# receiver.net
KiCad netlist of a schematic drawn in EAGLE
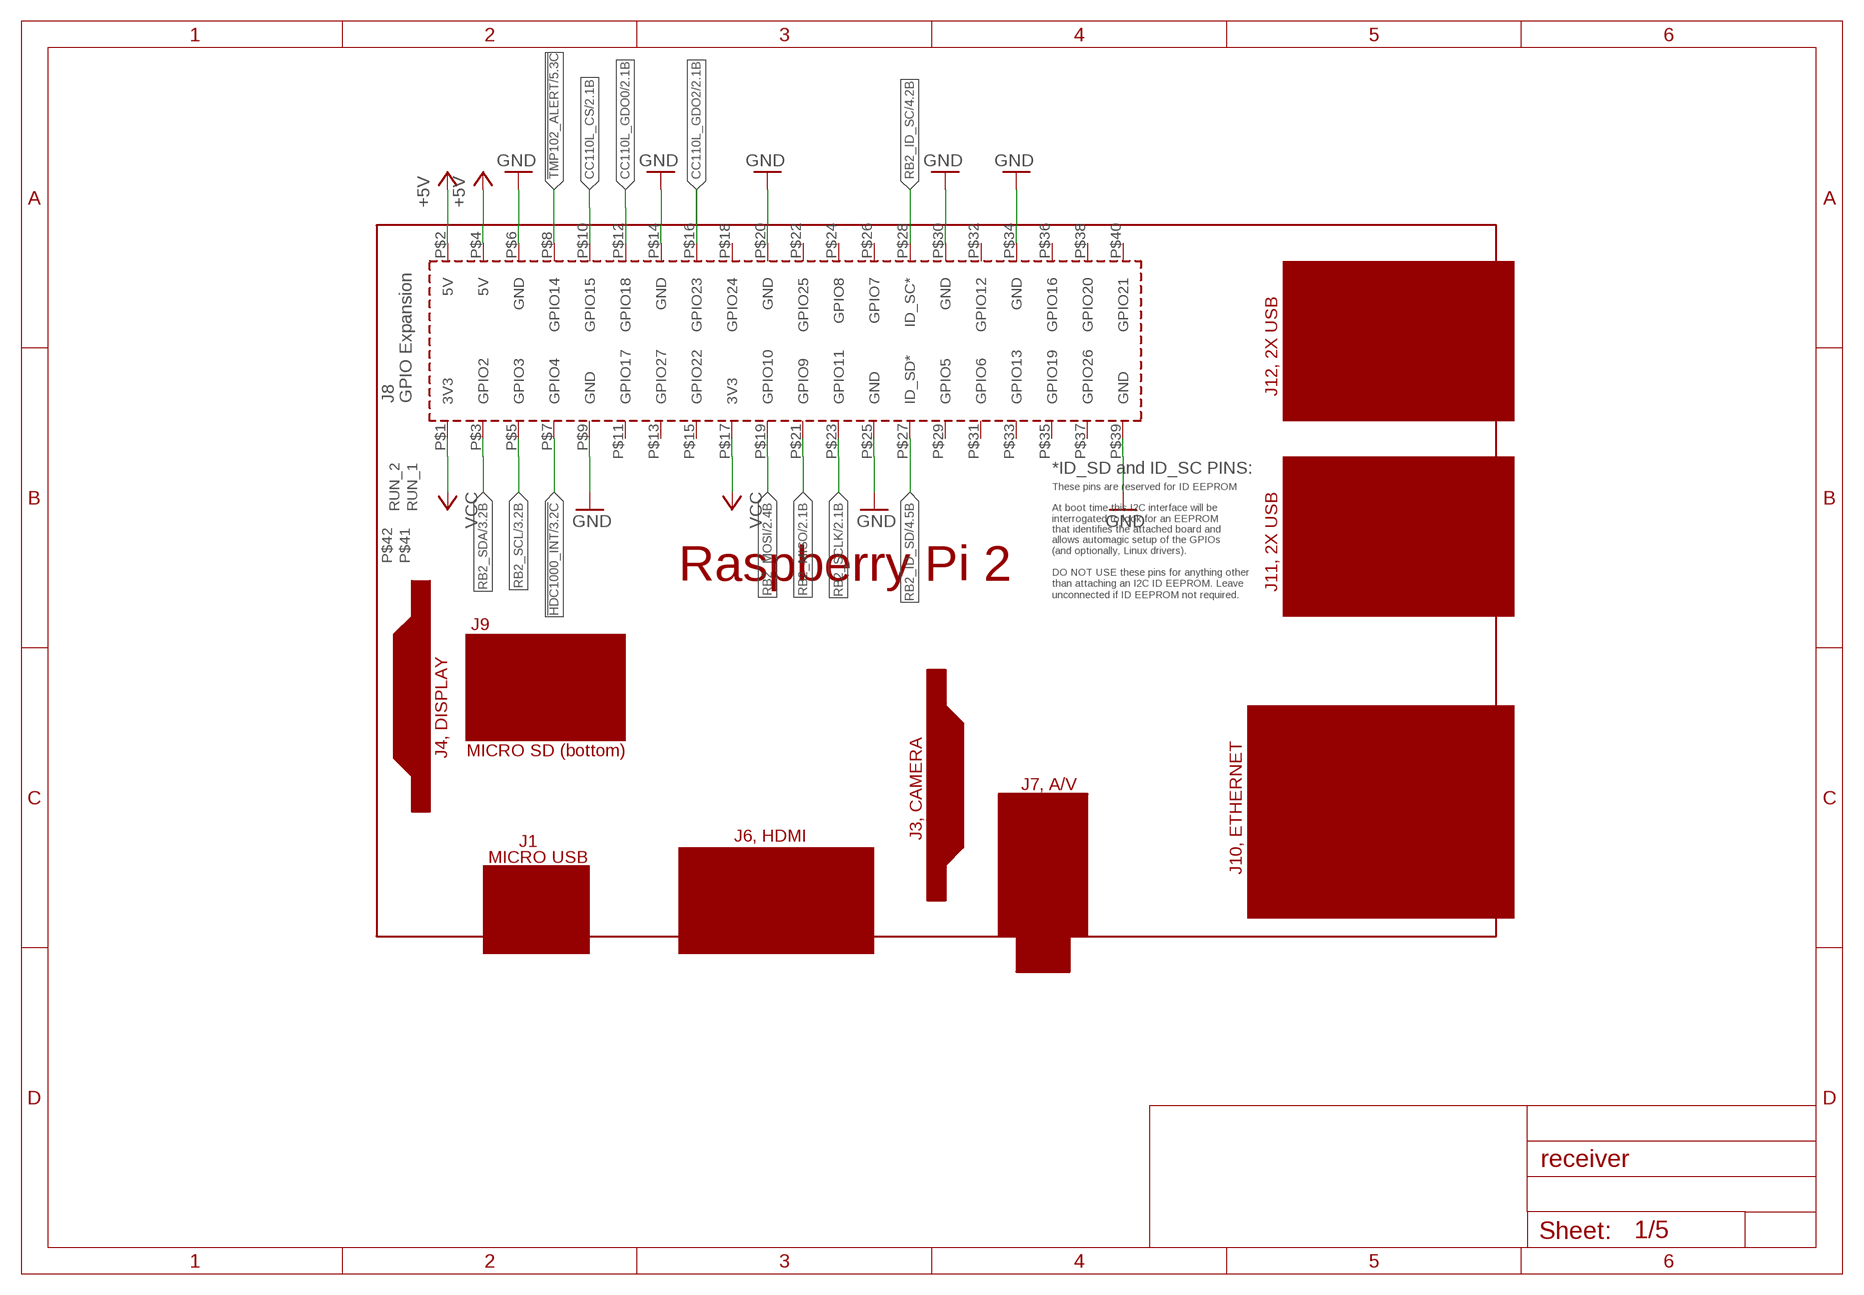
[diagram p0: schematic, sheet 1]
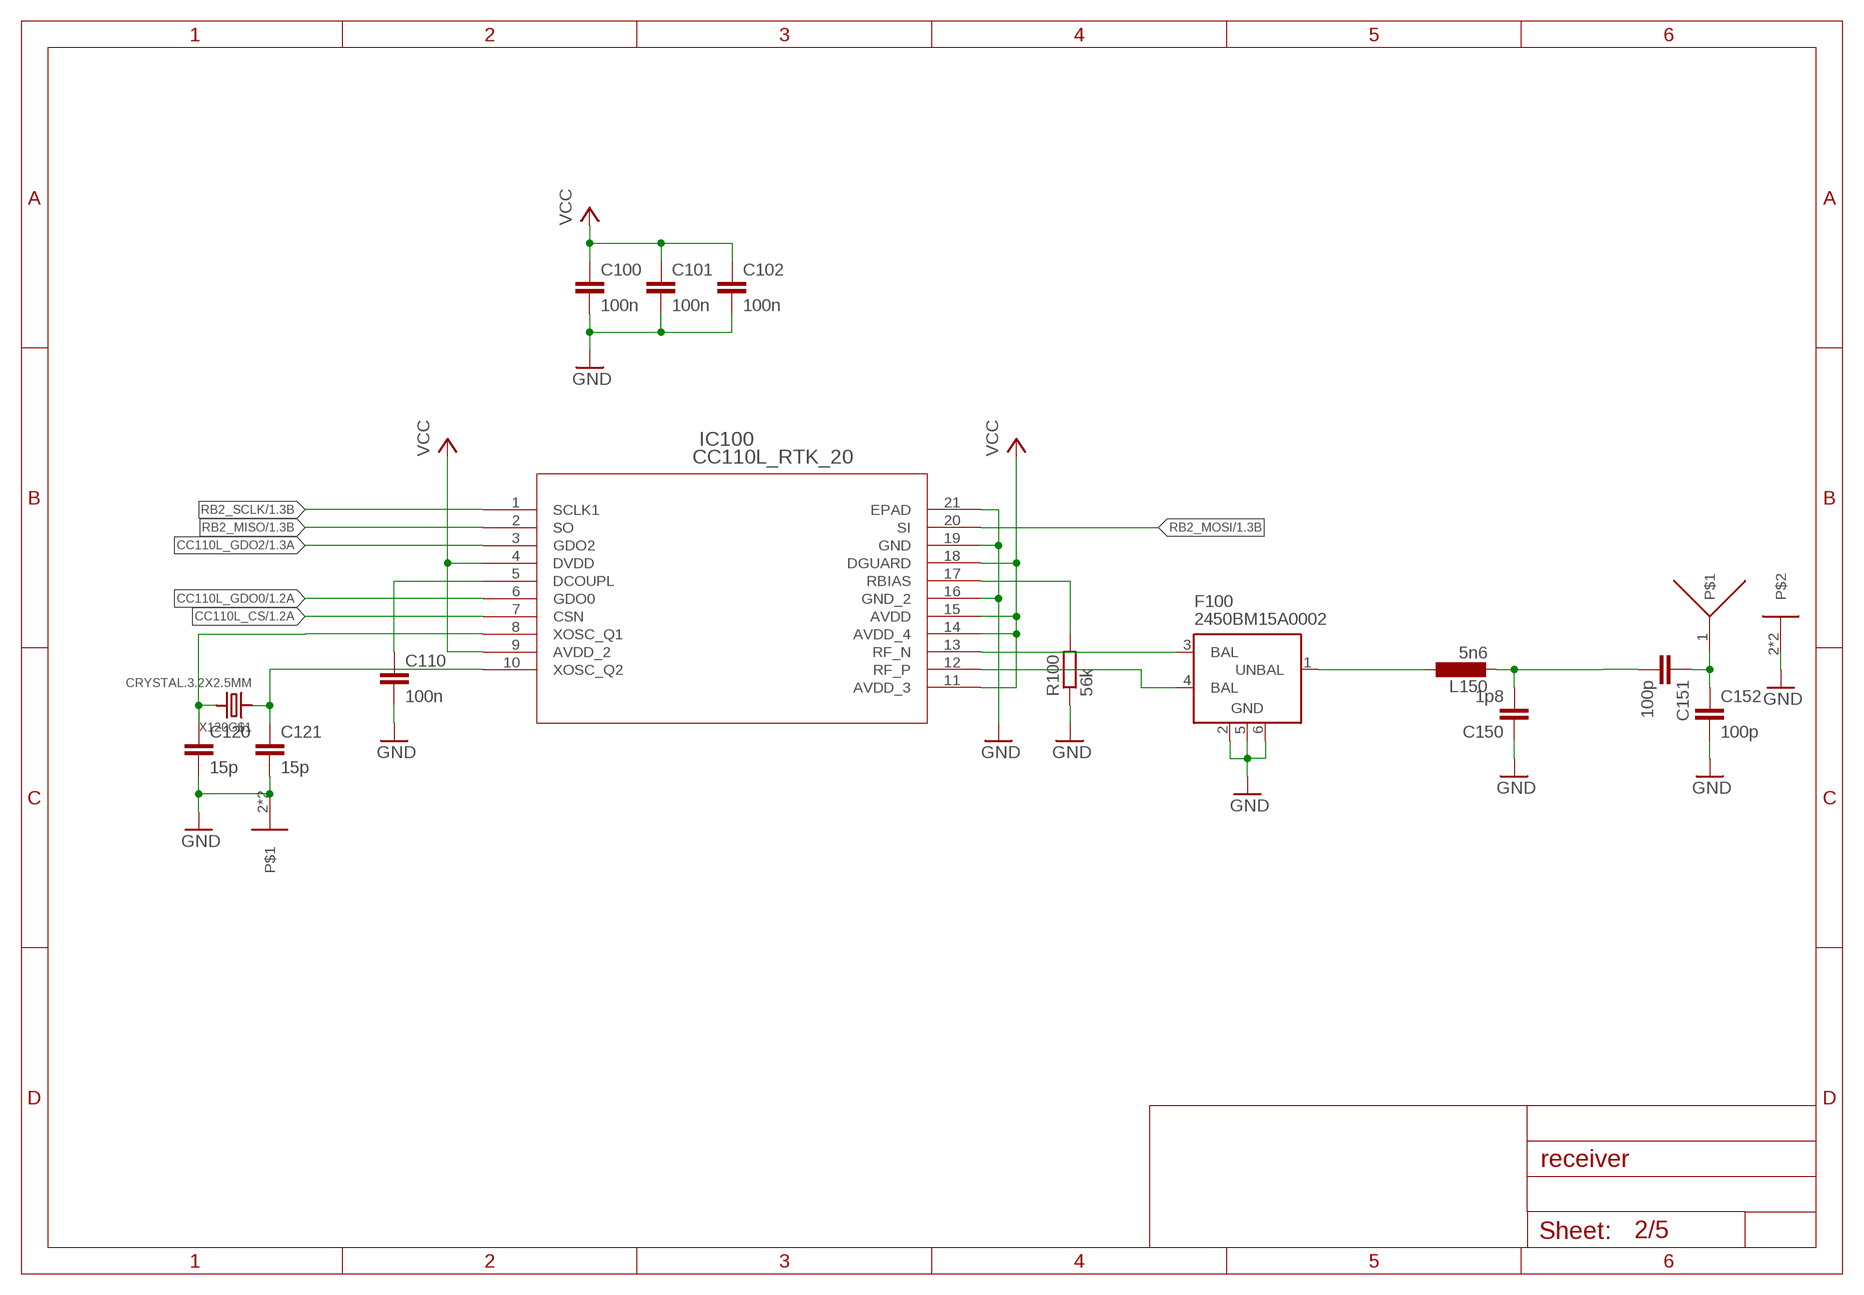
[diagram p1: schematic, sheet 2]
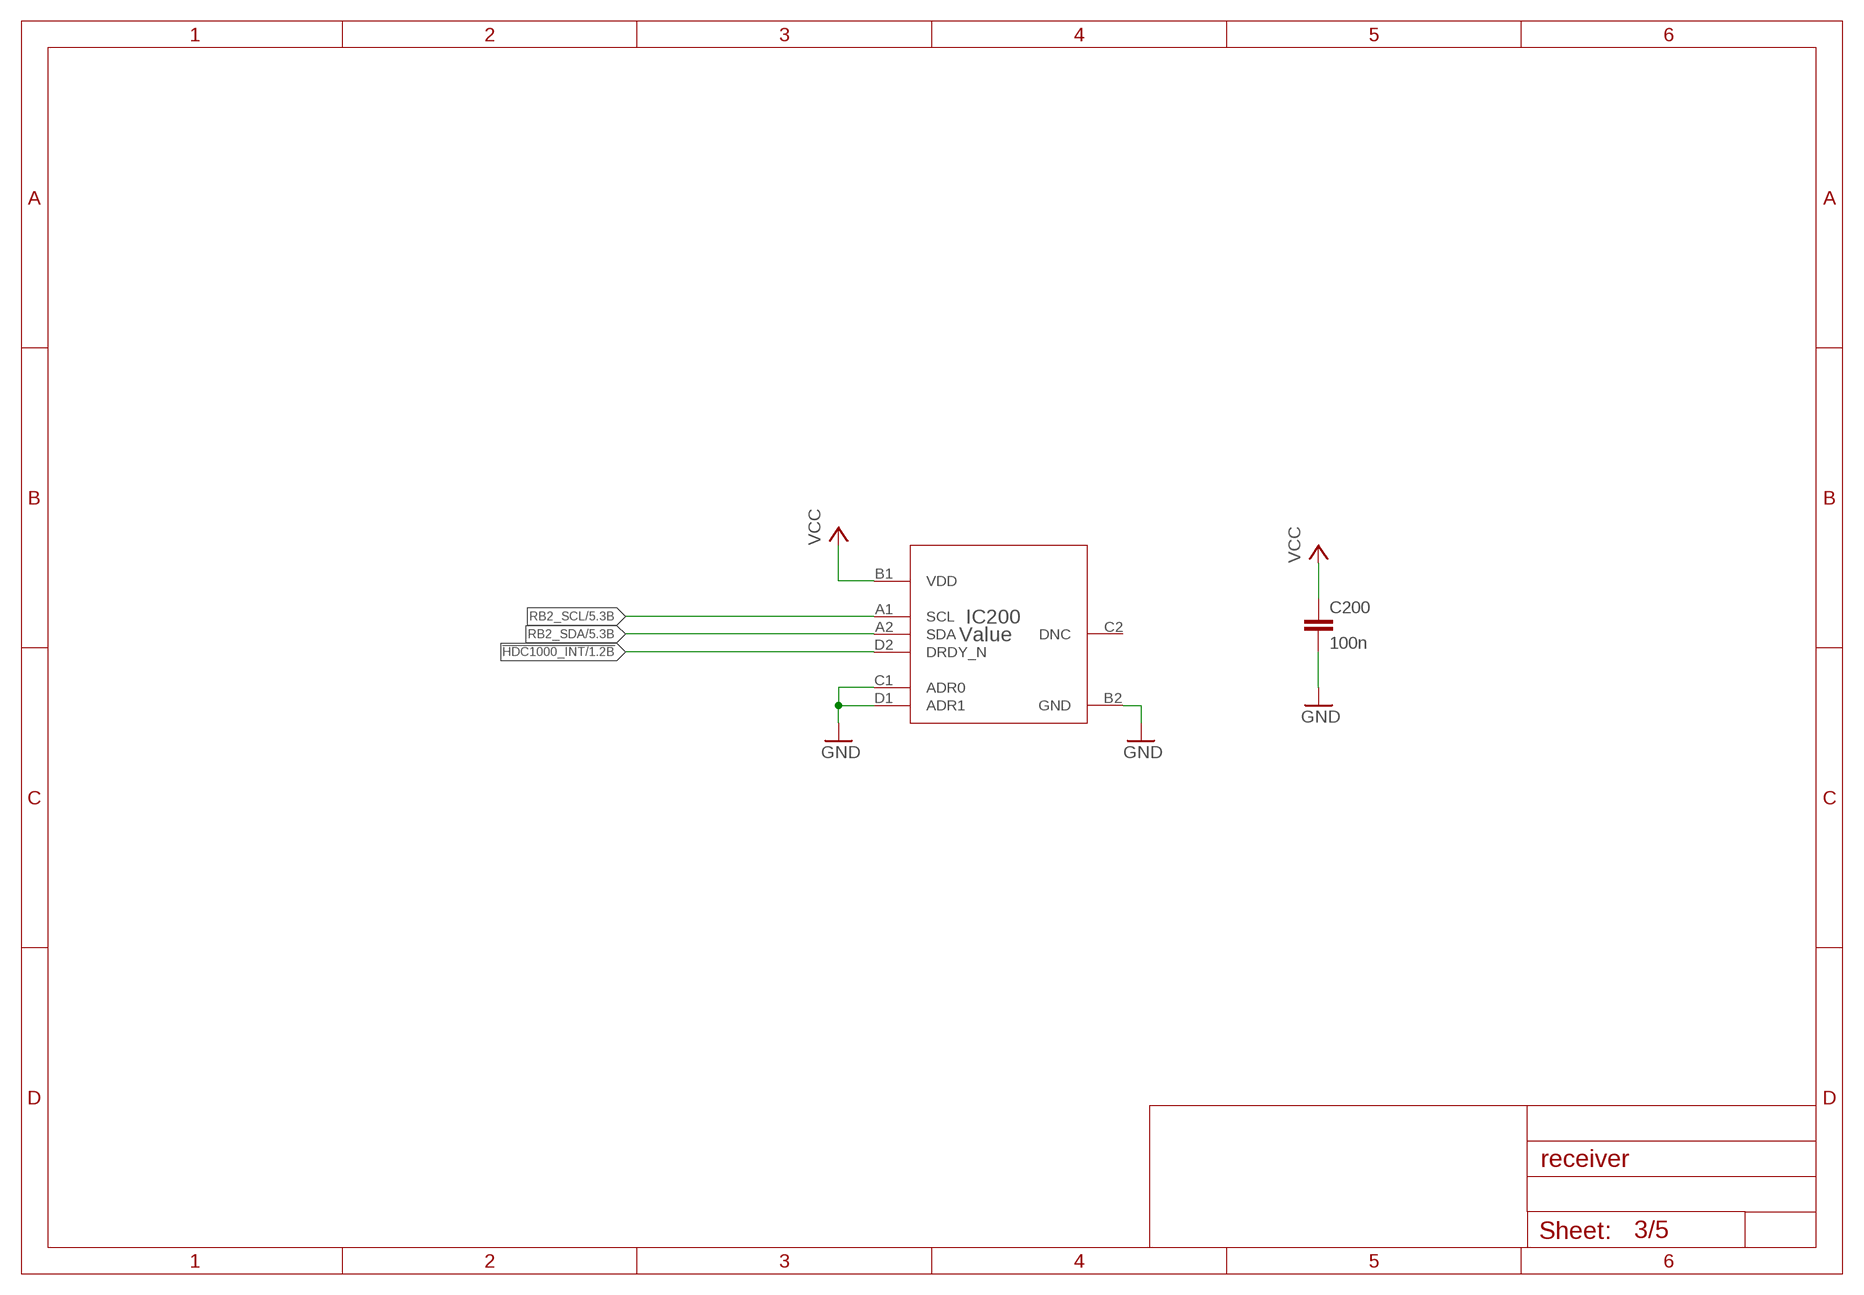
[diagram p2: schematic, sheet 3]
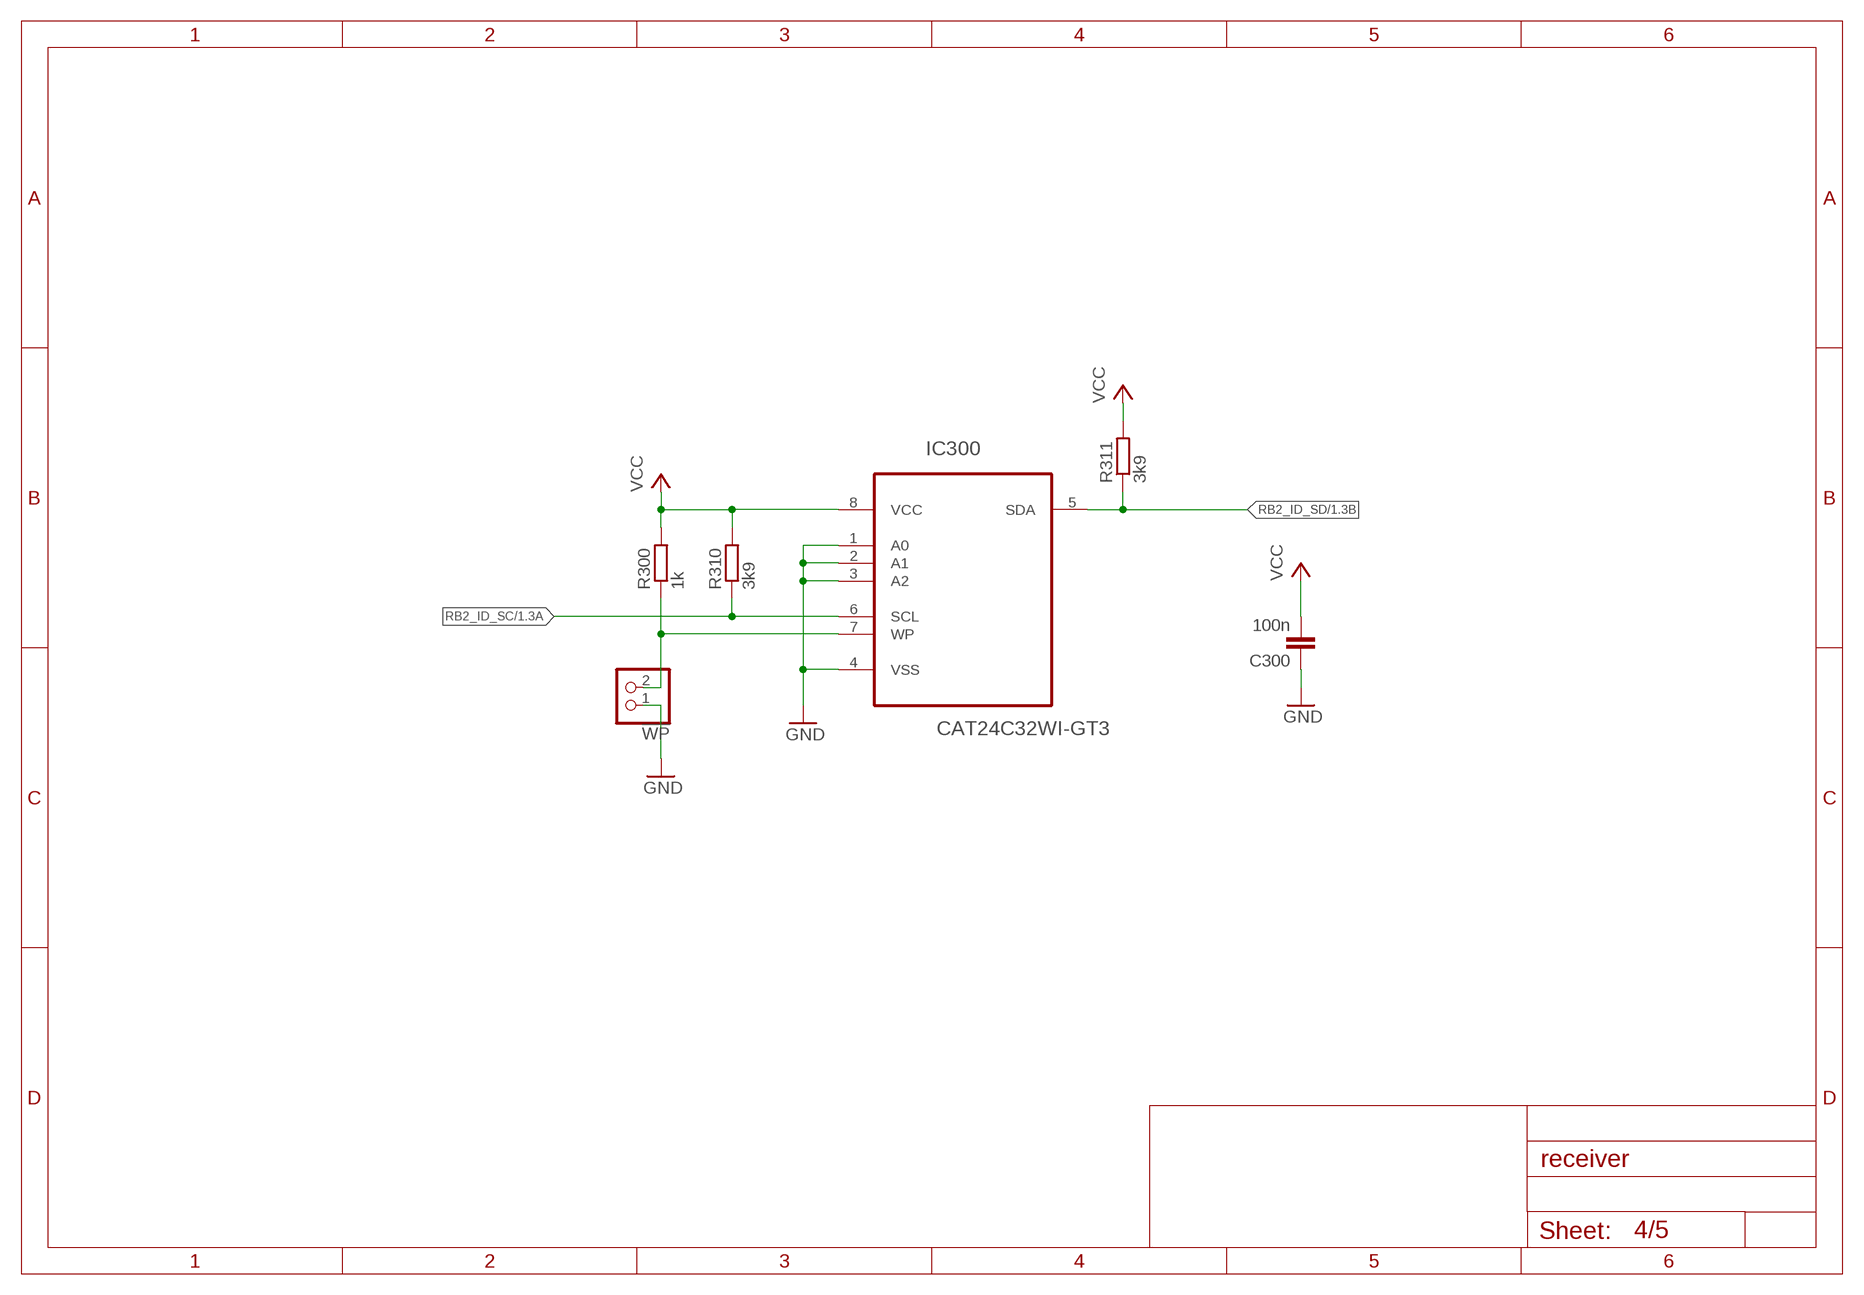
[diagram p3: schematic, sheet 4]
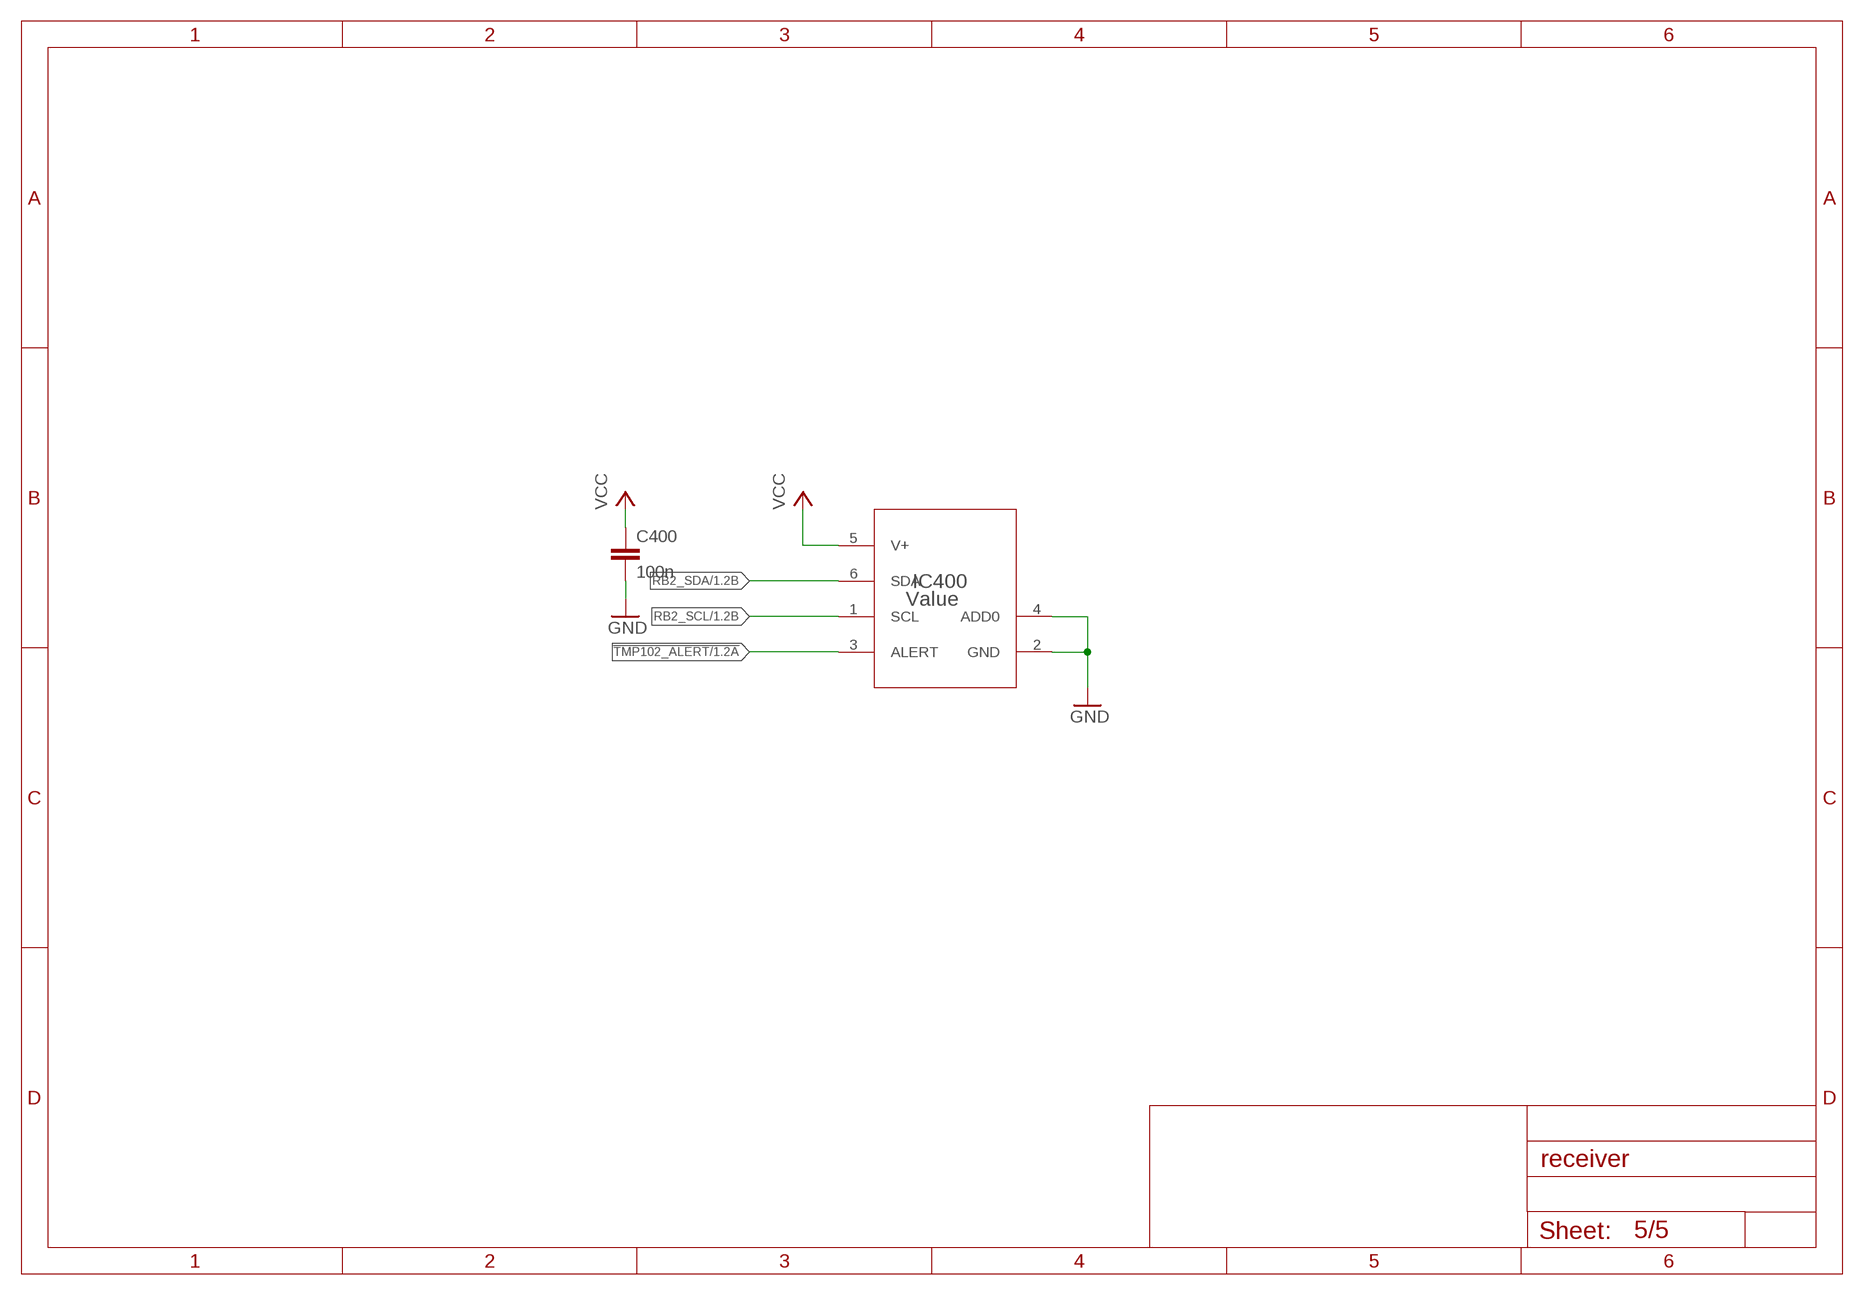
[diagram p4: schematic, sheet 5]

(export (version "E")
  (design (tool "Eeschema 10.0.6"))
  (components
    (comp (ref "C100")
      (value "100n")
      (footprint "eagle-import:C0603")
      (libsource (lib "eagle-import") (part "C-EUC0603"))
    )
    (comp (ref "C101")
      (value "100n")
      (footprint "eagle-import:C0603")
      (libsource (lib "eagle-import") (part "C-EUC0603"))
    )
    (comp (ref "C102")
      (value "100n")
      (footprint "eagle-import:C0603")
      (libsource (lib "eagle-import") (part "C-EUC0603"))
    )
    (comp (ref "C110")
      (value "100n")
      (footprint "eagle-import:C0603")
      (libsource (lib "eagle-import") (part "C-EUC0603"))
    )
    (comp (ref "C120")
      (value "15p")
      (footprint "eagle-import:C0603")
      (libsource (lib "eagle-import") (part "C-EUC0603"))
    )
    (comp (ref "C121")
      (value "15p")
      (footprint "eagle-import:C0603")
      (libsource (lib "eagle-import") (part "C-EUC0603"))
    )
    (comp (ref "C150")
      (value "1p8")
      (footprint "eagle-import:C0603K")
      (libsource (lib "eagle-import") (part "C-EUC0603K"))
    )
    (comp (ref "C151")
      (value "100p")
      (footprint "eagle-import:C0603")
      (libsource (lib "eagle-import") (part "C-EUC0603"))
    )
    (comp (ref "C152")
      (value "100p")
      (footprint "eagle-import:C0603K")
      (libsource (lib "eagle-import") (part "C-EUC0603K"))
    )
    (comp (ref "F100")
      (value "2450BM15A0002")
      (footprint "eagle-import:2450BM15A0002")
      (libsource (lib "eagle-import") (part "2450BM15A0002"))
    )
    (comp (ref "IC100")
      (value "CC110L_RTK_20")
      (footprint "eagle-import:RTK20_2P4X2P4")
      (fields (field (name "GENERIC_PART_NUMBER") "CC110L") (field (name "MANUFACTURER") "Texas Instruments"))
      (libsource (lib "eagle-import") (part "CC110L_RTK_20"))
    )
    (comp (ref "L150")
      (value "5n6")
      (footprint "eagle-import:L2012C")
      (libsource (lib "eagle-import") (part "L-EUL2012C"))
    )
    (comp (ref "R100")
      (value "56k")
      (footprint "eagle-import:R0603")
      (libsource (lib "eagle-import") (part "R-EU_R0603"))
    )
    (comp (ref "U$1")
      (value "ANTENNA868W3013-INV")
      (footprint "eagle-import:W3013-INV")
      (libsource (lib "eagle-import") (part "ANTENNA868W3013-INV"))
    )
    (comp (ref "X120")
      (value "CRYSTAL.3.2X2.5MM")
      (footprint "eagle-import:3.2X2.5MM")
      (libsource (lib "eagle-import") (part "CRYSTAL.3.2X2.5MM"))
    )
    (comp (ref "PCB1")
      (value "RPI2")
      (footprint "eagle-import:RPI2")
      (libsource (lib "eagle-import") (part "RPI2"))
    )
    (comp (ref "C200")
      (value "100n")
      (footprint "eagle-import:C0603")
      (libsource (lib "eagle-import") (part "C-EUC0603"))
    )
    (comp (ref "IC200")
      (value "Value")
      (footprint "eagle-import:YPA0008AGAE")
      (fields
        (field (name "ALTERNATEPARTNUMBER") "HDC1000YPAT")
        (field (name "MANUFACTURER") "Texas Instruments")
        (field (name "PARTNUMBER") "HDC1000YPAR")
      )
      (libsource (lib "eagle-import") (part "HDC1000YPAR"))
    )
    (comp (ref "C400")
      (value "100n")
      (footprint "eagle-import:C0603")
      (libsource (lib "eagle-import") (part "C-EUC0603"))
    )
    (comp (ref "IC400")
      (value "Value")
      (footprint "eagle-import:DRL0006A")
      (fields (field (name "MANUFACTURER") "Texas Instruments") (field (name "PARTNUMBER") "TMP102AQDRLRQ1"))
      (libsource (lib "eagle-import") (part "TMP102AQDRLRQ1"))
    )
    (comp (ref "!WP")
      (value "PINHD-1X2")
      (footprint "eagle-import:1X02")
      (libsource (lib "eagle-import") (part "PINHD-1X2"))
    )
    (comp (ref "C300")
      (value "100n")
      (footprint "eagle-import:C0603")
      (libsource (lib "eagle-import") (part "C-EUC0603"))
    )
    (comp (ref "IC300")
      (value "CAT24C32WI-GT3")
      (footprint "eagle-import:SOIC127P600X175-8N")
      (libsource (lib "eagle-import") (part "CAT24C32WI-GT3"))
    )
    (comp (ref "R300")
      (value "1k")
      (footprint "eagle-import:R0603")
      (libsource (lib "eagle-import") (part "R-EU_R0603"))
    )
    (comp (ref "R310")
      (value "3k9")
      (footprint "eagle-import:R0603")
      (libsource (lib "eagle-import") (part "R-EU_R0603"))
    )
    (comp (ref "R311")
      (value "3k9")
      (footprint "eagle-import:R0603")
      (libsource (lib "eagle-import") (part "R-EU_R0603"))
    )
  )
  (nets
    (net (code "1") (name "+5V") (class "Default")
      (node (ref "PCB1") (pin "P$2") (pinfunction "5V_P$2") (pintype "bidirectional"))
      (node (ref "PCB1") (pin "P$4") (pinfunction "5V_P$4") (pintype "bidirectional"))
    )
    (net (code "2") (name "CC110L_CS") (class "Default")
      (node (ref "IC100") (pin "7") (pinfunction "CSN_7") (pintype "passive"))
      (node (ref "PCB1") (pin "P$10") (pinfunction "GPIO15_P$10") (pintype "bidirectional"))
    )
    (net (code "3") (name "CC110L_GDO0") (class "Default")
      (node (ref "IC100") (pin "6") (pinfunction "GDO0_6") (pintype "output"))
      (node (ref "PCB1") (pin "P$12") (pinfunction "GPIO18_P$12") (pintype "bidirectional"))
    )
    (net (code "4") (name "CC110L_GDO2") (class "Default")
      (node (ref "IC100") (pin "3") (pinfunction "GDO2_3") (pintype "output"))
      (node (ref "PCB1") (pin "P$16") (pinfunction "GPIO23_P$16") (pintype "bidirectional"))
    )
    (net (code "5") (name "GND") (class "Default")
      (node (ref "!WP") (pin "1") (pinfunction "1_1") (pintype "passive"))
      (node (ref "C100") (pin "2") (pinfunction "2_2") (pintype "passive"))
      (node (ref "C101") (pin "2") (pinfunction "2_2") (pintype "passive"))
      (node (ref "C102") (pin "2") (pinfunction "2_2") (pintype "passive"))
      (node (ref "C110") (pin "2") (pinfunction "2_2") (pintype "passive"))
      (node (ref "C120") (pin "2") (pinfunction "2_2") (pintype "passive"))
      (node (ref "C121") (pin "2") (pinfunction "2_2") (pintype "passive"))
      (node (ref "C150") (pin "1") (pinfunction "1_1") (pintype "passive"))
      (node (ref "C152") (pin "2") (pinfunction "2_2") (pintype "passive"))
      (node (ref "C200") (pin "2") (pinfunction "2_2") (pintype "passive"))
      (node (ref "C300") (pin "1") (pinfunction "1_1") (pintype "passive"))
      (node (ref "C400") (pin "2") (pinfunction "2_2") (pintype "passive"))
      (node (ref "F100") (pin "2") (pinfunction "GND_2") (pintype "passive"))
      (node (ref "F100") (pin "5") (pinfunction "GND_5") (pintype "passive"))
      (node (ref "F100") (pin "6") (pinfunction "GND_6") (pintype "passive"))
      (node (ref "IC100") (pin "16") (pinfunction "GND_2_16") (pintype "power_in"))
      (node (ref "IC100") (pin "19") (pinfunction "GND_19") (pintype "power_in"))
      (node (ref "IC100") (pin "21") (pinfunction "EPAD_21") (pintype "power_in"))
      (node (ref "IC200") (pin "B2") (pinfunction "GND_B2") (pintype "power_in"))
      (node (ref "IC200") (pin "C1") (pinfunction "ADR0_C1") (pintype "input"))
      (node (ref "IC200") (pin "D1") (pinfunction "ADR1_D1") (pintype "input"))
      (node (ref "IC300") (pin "1") (pinfunction "A0_1") (pintype "input"))
      (node (ref "IC300") (pin "2") (pinfunction "A1_2") (pintype "input"))
      (node (ref "IC300") (pin "3") (pinfunction "A2_3") (pintype "input"))
      (node (ref "IC300") (pin "4") (pinfunction "VSS_4") (pintype "passive"))
      (node (ref "IC400") (pin "2") (pinfunction "GND_2") (pintype "power_in"))
      (node (ref "IC400") (pin "4") (pinfunction "ADD0_4") (pintype "input"))
      (node (ref "PCB1") (pin "P$14") (pinfunction "GND_P$14") (pintype "bidirectional"))
      (node (ref "PCB1") (pin "P$20") (pinfunction "GND_P$20") (pintype "bidirectional"))
      (node (ref "PCB1") (pin "P$25") (pinfunction "GND_P$25") (pintype "bidirectional"))
      (node (ref "PCB1") (pin "P$30") (pinfunction "GND_P$30") (pintype "bidirectional"))
      (node (ref "PCB1") (pin "P$34") (pinfunction "GND_P$34") (pintype "bidirectional"))
      (node (ref "PCB1") (pin "P$39") (pinfunction "GND_P$39") (pintype "bidirectional"))
      (node (ref "PCB1") (pin "P$6") (pinfunction "GND_P$6") (pintype "bidirectional"))
      (node (ref "PCB1") (pin "P$9") (pinfunction "GND_P$9") (pintype "bidirectional"))
      (node (ref "R100") (pin "1") (pinfunction "1_1") (pintype "passive"))
      (node (ref "U$1") (pin "2") (pinfunction "P$2_2") (pintype "bidirectional"))
      (node (ref "U$1") (pin "3") (pinfunction "P$2_3") (pintype "bidirectional"))
      (node (ref "X120") (pin "2") (pinfunction "P$1_2") (pintype "bidirectional"))
      (node (ref "X120") (pin "4") (pinfunction "P$1_4") (pintype "bidirectional"))
    )
    (net (code "6") (name "Net-(C150-Pad2)") (class "Default")
      (node (ref "C150") (pin "2") (pinfunction "2_2") (pintype "passive"))
      (node (ref "C151") (pin "2") (pinfunction "2_2") (pintype "passive"))
      (node (ref "L150") (pin "2") (pinfunction "2_2") (pintype "passive"))
    )
    (net (code "7") (name "Net-(F100-UNBAL)") (class "Default")
      (node (ref "F100") (pin "1") (pinfunction "UNBAL_1") (pintype "passive"))
      (node (ref "L150") (pin "1") (pinfunction "1_1") (pintype "passive"))
    )
    (net (code "8") (name "Net-(IC100-DCOUPL)") (class "Default")
      (node (ref "C110") (pin "1") (pinfunction "1_1") (pintype "passive"))
      (node (ref "IC100") (pin "5") (pinfunction "DCOUPL_5") (pintype "passive"))
    )
    (net (code "9") (name "Net-(IC100-RBIAS)") (class "Default")
      (node (ref "IC100") (pin "17") (pinfunction "RBIAS_17") (pintype "passive"))
      (node (ref "R100") (pin "2") (pinfunction "2_2") (pintype "passive"))
    )
    (net (code "10") (name "Net-(IC100-RF_N)") (class "Default")
      (node (ref "F100") (pin "3") (pinfunction "BAL_3") (pintype "passive"))
      (node (ref "IC100") (pin "13") (pinfunction "RF_N_13") (pintype "passive"))
    )
    (net (code "11") (name "Net-(IC100-RF_P)") (class "Default")
      (node (ref "F100") (pin "4") (pinfunction "BAL_4") (pintype "passive"))
      (node (ref "IC100") (pin "12") (pinfunction "RF_P_12") (pintype "passive"))
    )
    (net (code "12") (name "Net-(IC100-XOSC_Q1)") (class "Default")
      (node (ref "C120") (pin "1") (pinfunction "1_1") (pintype "passive"))
      (node (ref "IC100") (pin "8") (pinfunction "XOSC_Q1_8") (pintype "passive"))
      (node (ref "X120") (pin "3") (pinfunction "2_3") (pintype "passive"))
    )
    (net (code "13") (name "Net-(IC100-XOSC_Q2)") (class "Default")
      (node (ref "C121") (pin "1") (pinfunction "1_1") (pintype "passive"))
      (node (ref "IC100") (pin "10") (pinfunction "XOSC_Q2_10") (pintype "passive"))
      (node (ref "X120") (pin "1") (pinfunction "1_1") (pintype "passive"))
    )
    (net (code "14") (name "Net-(IC300-WP)") (class "Default")
      (node (ref "!WP") (pin "2") (pinfunction "2_2") (pintype "passive"))
      (node (ref "IC300") (pin "7") (pinfunction "WP_7") (pintype "input"))
      (node (ref "R300") (pin "1") (pinfunction "1_1") (pintype "passive"))
    )
    (net (code "15") (name "Net-(U$1-P$1)") (class "Default")
      (node (ref "C151") (pin "1") (pinfunction "1_1") (pintype "passive"))
      (node (ref "C152") (pin "1") (pinfunction "1_1") (pintype "passive"))
      (node (ref "U$1") (pin "1") (pinfunction "P$1_1") (pintype "bidirectional"))
    )
    (net (code "16") (name "RB2_ID_SC") (class "Default")
      (node (ref "IC300") (pin "6") (pinfunction "SCL_6") (pintype "input"))
      (node (ref "PCB1") (pin "P$28") (pinfunction "ID_SC*_P$28") (pintype "bidirectional"))
      (node (ref "R310") (pin "1") (pinfunction "1_1") (pintype "passive"))
    )
    (net (code "17") (name "RB2_ID_SD") (class "Default")
      (node (ref "IC300") (pin "5") (pinfunction "SDA_5") (pintype "bidirectional"))
      (node (ref "PCB1") (pin "P$27") (pinfunction "ID_SD*_P$27") (pintype "bidirectional"))
      (node (ref "R311") (pin "1") (pinfunction "1_1") (pintype "passive"))
    )
    (net (code "18") (name "RB2_MISO") (class "Default")
      (node (ref "IC100") (pin "2") (pinfunction "SO_2") (pintype "output"))
      (node (ref "PCB1") (pin "P$21") (pinfunction "GPIO9_P$21") (pintype "bidirectional"))
    )
    (net (code "19") (name "RB2_MOSI") (class "Default")
      (node (ref "IC100") (pin "20") (pinfunction "SI_20") (pintype "input"))
      (node (ref "PCB1") (pin "P$19") (pinfunction "GPIO10_P$19") (pintype "bidirectional"))
    )
    (net (code "20") (name "RB2_SCL") (class "Default")
      (node (ref "IC200") (pin "A1") (pinfunction "SCL_A1") (pintype "input"))
      (node (ref "IC400") (pin "1") (pinfunction "SCL_1") (pintype "bidirectional"))
      (node (ref "PCB1") (pin "P$5") (pinfunction "GPIO3_P$5") (pintype "bidirectional"))
    )
    (net (code "21") (name "RB2_SCLK") (class "Default")
      (node (ref "IC100") (pin "1") (pinfunction "SCLK1_1") (pintype "passive"))
      (node (ref "PCB1") (pin "P$23") (pinfunction "GPIO11_P$23") (pintype "bidirectional"))
    )
    (net (code "22") (name "RB2_SDA") (class "Default")
      (node (ref "IC200") (pin "A2") (pinfunction "SDA_A2") (pintype "bidirectional"))
      (node (ref "IC400") (pin "6") (pinfunction "SDA_6") (pintype "bidirectional"))
      (node (ref "PCB1") (pin "P$3") (pinfunction "GPIO2_P$3") (pintype "bidirectional"))
    )
    (net (code "23") (name "VCC") (class "Default")
      (node (ref "C100") (pin "1") (pinfunction "1_1") (pintype "passive"))
      (node (ref "C101") (pin "1") (pinfunction "1_1") (pintype "passive"))
      (node (ref "C102") (pin "1") (pinfunction "1_1") (pintype "passive"))
      (node (ref "C200") (pin "1") (pinfunction "1_1") (pintype "passive"))
      (node (ref "C300") (pin "2") (pinfunction "2_2") (pintype "passive"))
      (node (ref "C400") (pin "1") (pinfunction "1_1") (pintype "passive"))
      (node (ref "IC100") (pin "11") (pinfunction "AVDD_3_11") (pintype "power_in"))
      (node (ref "IC100") (pin "14") (pinfunction "AVDD_4_14") (pintype "power_in"))
      (node (ref "IC100") (pin "15") (pinfunction "AVDD_15") (pintype "power_in"))
      (node (ref "IC100") (pin "18") (pinfunction "DGUARD_18") (pintype "passive"))
      (node (ref "IC100") (pin "4") (pinfunction "DVDD_4") (pintype "power_in"))
      (node (ref "IC100") (pin "9") (pinfunction "AVDD_2_9") (pintype "power_in"))
      (node (ref "IC200") (pin "B1") (pinfunction "VDD_B1") (pintype "power_in"))
      (node (ref "IC300") (pin "8") (pinfunction "VCC_8") (pintype "power_in"))
      (node (ref "IC400") (pin "5") (pinfunction "V+_5") (pintype "power_in"))
      (node (ref "PCB1") (pin "P$1") (pinfunction "3V3_P$1") (pintype "bidirectional"))
      (node (ref "PCB1") (pin "P$17") (pinfunction "3V3_P$17") (pintype "bidirectional"))
      (node (ref "R300") (pin "2") (pinfunction "2_2") (pintype "passive"))
      (node (ref "R310") (pin "2") (pinfunction "2_2") (pintype "passive"))
      (node (ref "R311") (pin "2") (pinfunction "2_2") (pintype "passive"))
    )
    (net (code "24") (name "unconnected-(IC200-DNC-PadC2)") (class "Default")
      (node (ref "IC200") (pin "C2") (pinfunction "DNC_C2") (pintype "passive"))
    )
    (net (code "25") (name "unconnected-(PCB1-GPIO5-PadP$29)") (class "Default")
      (node (ref "PCB1") (pin "P$29") (pinfunction "GPIO5_P$29") (pintype "bidirectional"))
    )
    (net (code "26") (name "unconnected-(PCB1-GPIO6-PadP$31)") (class "Default")
      (node (ref "PCB1") (pin "P$31") (pinfunction "GPIO6_P$31") (pintype "bidirectional"))
    )
    (net (code "27") (name "unconnected-(PCB1-GPIO7-PadP$26)") (class "Default")
      (node (ref "PCB1") (pin "P$26") (pinfunction "GPIO7_P$26") (pintype "bidirectional"))
    )
    (net (code "28") (name "unconnected-(PCB1-GPIO8-PadP$24)") (class "Default")
      (node (ref "PCB1") (pin "P$24") (pinfunction "GPIO8_P$24") (pintype "bidirectional"))
    )
    (net (code "29") (name "unconnected-(PCB1-GPIO12-PadP$32)") (class "Default")
      (node (ref "PCB1") (pin "P$32") (pinfunction "GPIO12_P$32") (pintype "bidirectional"))
    )
    (net (code "30") (name "unconnected-(PCB1-GPIO13-PadP$33)") (class "Default")
      (node (ref "PCB1") (pin "P$33") (pinfunction "GPIO13_P$33") (pintype "bidirectional"))
    )
    (net (code "31") (name "unconnected-(PCB1-GPIO16-PadP$36)") (class "Default")
      (node (ref "PCB1") (pin "P$36") (pinfunction "GPIO16_P$36") (pintype "bidirectional"))
    )
    (net (code "32") (name "unconnected-(PCB1-GPIO17-PadP$11)") (class "Default")
      (node (ref "PCB1") (pin "P$11") (pinfunction "GPIO17_P$11") (pintype "bidirectional"))
    )
    (net (code "33") (name "unconnected-(PCB1-GPIO19-PadP$35)") (class "Default")
      (node (ref "PCB1") (pin "P$35") (pinfunction "GPIO19_P$35") (pintype "bidirectional"))
    )
    (net (code "34") (name "unconnected-(PCB1-GPIO20-PadP$38)") (class "Default")
      (node (ref "PCB1") (pin "P$38") (pinfunction "GPIO20_P$38") (pintype "bidirectional"))
    )
    (net (code "35") (name "unconnected-(PCB1-GPIO21-PadP$40)") (class "Default")
      (node (ref "PCB1") (pin "P$40") (pinfunction "GPIO21_P$40") (pintype "bidirectional"))
    )
    (net (code "36") (name "unconnected-(PCB1-GPIO22-PadP$15)") (class "Default")
      (node (ref "PCB1") (pin "P$15") (pinfunction "GPIO22_P$15") (pintype "bidirectional"))
    )
    (net (code "37") (name "unconnected-(PCB1-GPIO24-PadP$18)") (class "Default")
      (node (ref "PCB1") (pin "P$18") (pinfunction "GPIO24_P$18") (pintype "bidirectional"))
    )
    (net (code "38") (name "unconnected-(PCB1-GPIO25-PadP$22)") (class "Default")
      (node (ref "PCB1") (pin "P$22") (pinfunction "GPIO25_P$22") (pintype "bidirectional"))
    )
    (net (code "39") (name "unconnected-(PCB1-GPIO26-PadP$37)") (class "Default")
      (node (ref "PCB1") (pin "P$37") (pinfunction "GPIO26_P$37") (pintype "bidirectional"))
    )
    (net (code "40") (name "unconnected-(PCB1-GPIO27-PadP$13)") (class "Default")
      (node (ref "PCB1") (pin "P$13") (pinfunction "GPIO27_P$13") (pintype "bidirectional"))
    )
    (net (code "41") (name "unconnected-(PCB1-RUN_1-PadP$41)") (class "Default")
      (node (ref "PCB1") (pin "P$41") (pinfunction "RUN_1_P$41") (pintype "bidirectional"))
    )
    (net (code "42") (name "unconnected-(PCB1-RUN_2-PadP$42)") (class "Default")
      (node (ref "PCB1") (pin "P$42") (pinfunction "RUN_2_P$42") (pintype "bidirectional"))
    )
    (net (code "43") (name "~{HDC1000_INT}") (class "Default")
      (node (ref "IC200") (pin "D2") (pinfunction "DRDY_N_D2") (pintype "input"))
      (node (ref "PCB1") (pin "P$7") (pinfunction "GPIO4_P$7") (pintype "bidirectional"))
    )
    (net (code "44") (name "~{TMP102_ALERT}") (class "Default")
      (node (ref "IC400") (pin "3") (pinfunction "ALERT_3") (pintype "output"))
      (node (ref "PCB1") (pin "P$8") (pinfunction "GPIO14_P$8") (pintype "bidirectional"))
    )
  )
)
